# 2_MaxWatch.net
KiCad netlist of a schematic drawn in Altium Designer
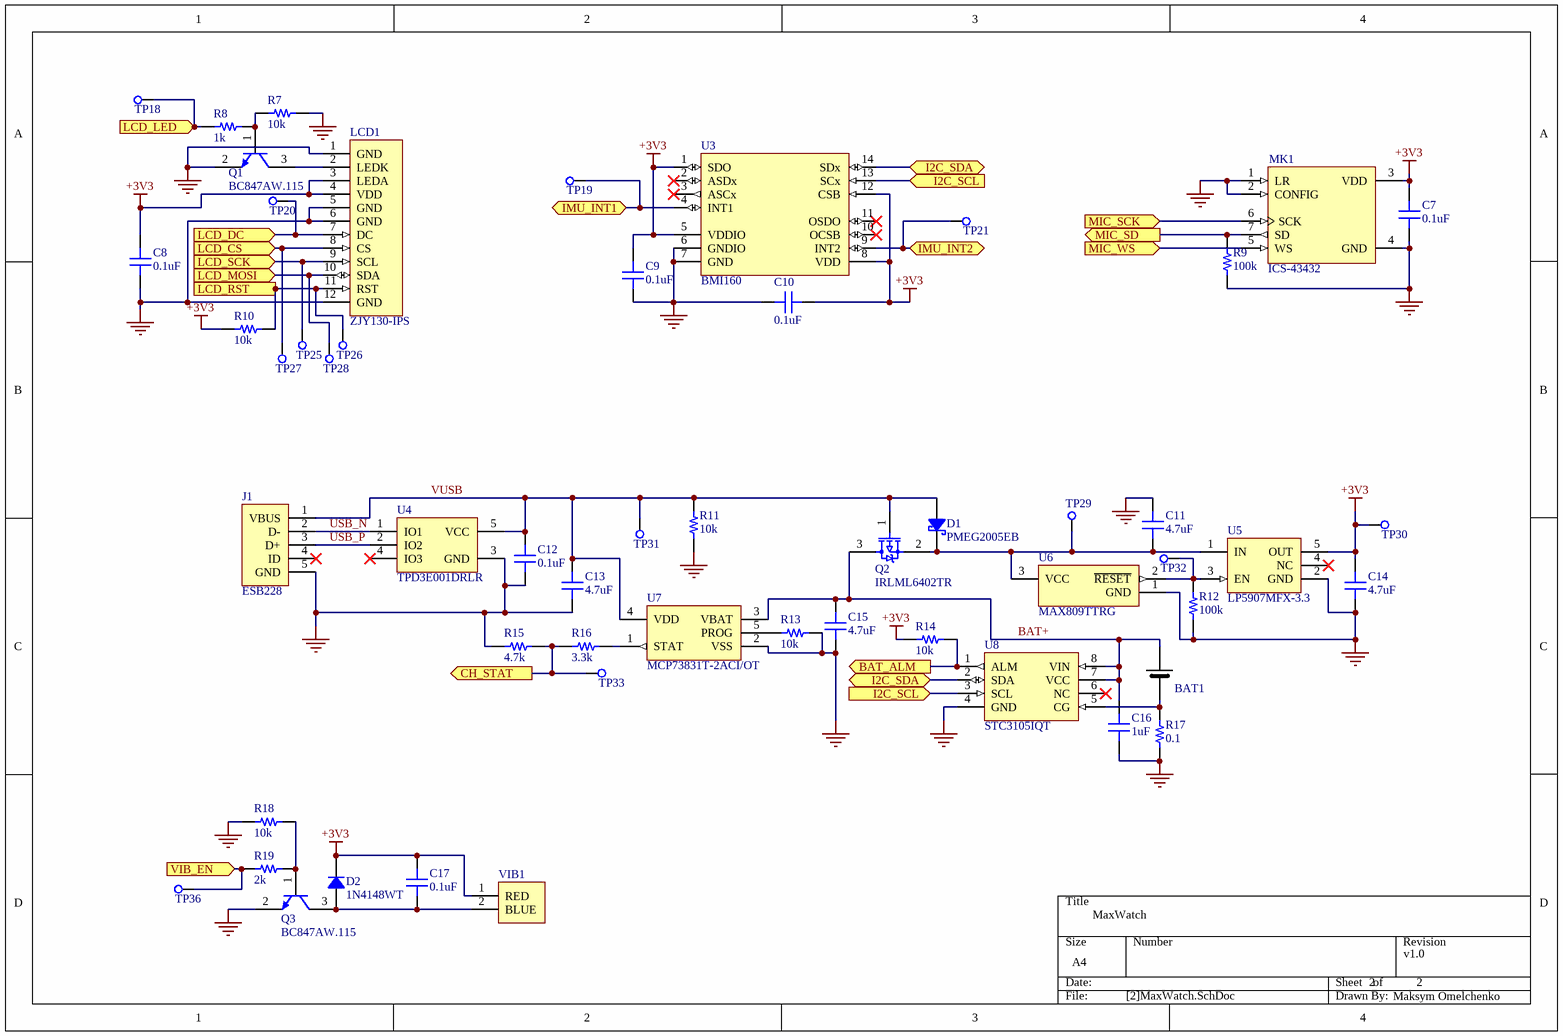
[diagram p0: [2]MaxWatch.SchDoc]

(export (version "E")
  (design (tool "Eeschema 10.0.6"))
  (components
    (comp (ref "BAT1")
      (value "Lipo battery")
      (footprint "PCBComponent_1")
      (libsource (lib "Battery") (part "Lipo_battery"))
    )
    (comp (ref "C7")
      (value "0.1uF")
      (footprint "CAP 0402/1005")
      (description "CAP CER 0.1UF 16V X7R 0402")
      (fields
        (field (name "PART NUMBER") "C1005X7R1C104K050BC")
        (field (name "MANUFACTURER") "TDK Corporation")
      )
      (libsource (lib "Celestial Library Database") (part "Capacitor"))
    )
    (comp (ref "C8")
      (value "0.1uF")
      (footprint "CAP 0402/1005")
      (description "CAP CER 0.1UF 16V X7R 0402")
      (fields
        (field (name "PART NUMBER") "C1005X7R1C104K050BC")
        (field (name "MANUFACTURER") "TDK Corporation")
      )
      (libsource (lib "Celestial Library Database") (part "Capacitor"))
    )
    (comp (ref "C9")
      (value "0.1uF")
      (footprint "CAP 0402/1005")
      (description "CAP CER 0.1UF 16V X7R 0402")
      (fields
        (field (name "PART NUMBER") "C1005X7R1C104K050BC")
        (field (name "MANUFACTURER") "TDK Corporation")
      )
      (libsource (lib "Celestial Library Database") (part "Capacitor"))
    )
    (comp (ref "C10")
      (value "0.1uF")
      (footprint "CAP 0402/1005")
      (description "CAP CER 0.1UF 16V X7R 0402")
      (fields
        (field (name "PART NUMBER") "C1005X7R1C104K050BC")
        (field (name "MANUFACTURER") "TDK Corporation")
      )
      (libsource (lib "Celestial Library Database") (part "Capacitor"))
    )
    (comp (ref "C11")
      (value "4.7uF")
      (footprint "CAP 0603/1608")
      (description "CAP CER 4.7UF 6.3V X5R 0603")
      (fields (field (name "PART NUMBER") "JMK107BJ475KA-T") (field (name "MANUFACTURER") "Taiyo Yuden"))
      (libsource (lib "Celestial Library Database") (part "Capacitor"))
    )
    (comp (ref "C12")
      (value "0.1uF")
      (footprint "CAP 0402/1005")
      (description "CAP CER 0.1UF 16V X7R 0402")
      (fields
        (field (name "PART NUMBER") "C1005X7R1C104K050BC")
        (field (name "MANUFACTURER") "TDK Corporation")
      )
      (libsource (lib "Celestial Library Database") (part "Capacitor"))
    )
    (comp (ref "C13")
      (value "4.7uF")
      (footprint "CAP 0603/1608")
      (description "CAP CER 4.7UF 6.3V X5R 0603")
      (fields (field (name "PART NUMBER") "JMK107BJ475KA-T") (field (name "MANUFACTURER") "Taiyo Yuden"))
      (libsource (lib "Celestial Library Database") (part "Capacitor"))
    )
    (comp (ref "C14")
      (value "4.7uF")
      (footprint "CAP 0603/1608")
      (description "CAP CER 4.7UF 6.3V X5R 0603")
      (fields (field (name "PART NUMBER") "JMK107BJ475KA-T") (field (name "MANUFACTURER") "Taiyo Yuden"))
      (libsource (lib "Celestial Library Database") (part "Capacitor"))
    )
    (comp (ref "C15")
      (value "4.7uF")
      (footprint "CAP 0603/1608")
      (description "CAP CER 4.7UF 6.3V X5R 0603")
      (fields (field (name "PART NUMBER") "JMK107BJ475KA-T") (field (name "MANUFACTURER") "Taiyo Yuden"))
      (libsource (lib "Celestial Library Database") (part "Capacitor"))
    )
    (comp (ref "C16")
      (value "1uF")
      (footprint "CAP 0402/1005")
      (description "CAP CER 1UF 4V X7R 0402")
      (fields
        (field (name "PART NUMBER") "GRM155R70G105KA12D")
        (field (name "MANUFACTURER") "Murata Electronics North America")
      )
      (libsource (lib "Celestial Library Database") (part "Capacitor"))
    )
    (comp (ref "C17")
      (value "0.1uF")
      (footprint "CAP 0402/1005")
      (description "CAP CER 0.1UF 16V X7R 0402")
      (fields
        (field (name "PART NUMBER") "C1005X7R1C104K050BC")
        (field (name "MANUFACTURER") "TDK Corporation")
      )
      (libsource (lib "Celestial Library Database") (part "Capacitor"))
    )
    (comp (ref "D1")
      (value "PMEG2005EB")
      (footprint "NXP-SOD-523F-2_V")
      (fields (field (name "MANUFACTURER") "Nexperia") (field (name "MODEL") "PMEG2005EB"))
      (libsource (lib "Nexperia_PMEG2005EB") (part "PMEG2005EB"))
    )
    (comp (ref "D2")
      (value "1N4148WT")
      (footprint "FAIR-SOD-523F-2_V")
      (description "High Conductance Fast Switching Diode, 75 V, -55 to 150 degC, 2-Pin SOD523F, RoHS")
      (fields (field (name "MANUFACTURER") "Fairchild Semiconductor") (field (name "PARTNUMBER") "1N4148WT"))
      (libsource (lib "1N4148WT") (part "1N4148WT"))
    )
    (comp (ref "J1")
      (value "ESB228")
      (footprint "EXB228")
      (fields (field (name "MODEL") "ESB228"))
      (libsource (lib "ESB228") (part "ESB228"))
    )
    (comp (ref "LCD1")
      (value "ZJY130-IPS ST7789 based lcd display")
      (footprint "ZJY130-IPS")
      (fields (field (name "MODEL") "ZJY130-IPS"))
      (libsource (lib "ZJY130-IPS") (part "ZJY130-IPS"))
    )
    (comp (ref "MK1")
      (value "ICS-43432")
      (footprint "MIC_ICS-43432")
      (description "A high performance, low power, digital output, omnidirectional MEMS microphone with a bottom port.")
      (fields (field (name "MF") "TDK InvenSense") (field (name "MODEL") "ICS-43432"))
      (libsource (lib "ICS-43432") (part "ICS-43432"))
    )
    (comp (ref "Q1")
      (value "BC847AW")
      (footprint "NEXPERIA-SC-70")
      (description "General Purpose Transistor, NPN Silicon, 3-Pin SC70, Tape and Reel")
      (fields (field (name "MANUFACTURER") "Nexperia") (field (name "MODEL") "BC847AW.115"))
      (libsource (lib "BC847AW") (part "BC847AW"))
    )
    (comp (ref "Q2")
      (value "IRLML6402TRPBF")
      (footprint "Infineon_SOT23")
      (fields (field (name "MANUFACTURER") "Infineon Technologies") (field (name "MODEL") "IRLML6402TR"))
      (libsource (lib "IRLML6402TR") (part "IRLML6402TRPBF"))
    )
    (comp (ref "Q3")
      (value "BC847AW")
      (footprint "NEXPERIA-SC-70")
      (description "General Purpose Transistor, NPN Silicon, 3-Pin SC70, Tape and Reel")
      (fields (field (name "MANUFACTURER") "Nexperia") (field (name "MODEL") "BC847AW.115"))
      (libsource (lib "BC847AW") (part "BC847AW"))
    )
    (comp (ref "R7")
      (value "10k")
      (footprint "RES 0201/0603")
      (description "RES SMD 10K OHM 5% 1/20W 0201")
      (fields (field (name "PART NUMBER") "RC0201JR-0710KL") (field (name "MANUFACTURER") "Yageo"))
      (libsource (lib "Celestial Library Database") (part "Resistor"))
    )
    (comp (ref "R8")
      (value "1k")
      (footprint "RES 0402/1005")
      (description "RES SMD 1K OHM 1% 1/10W 0402")
      (fields
        (field (name "PART NUMBER") "ERJ-2RKF1001X")
        (field (name "MANUFACTURER") "Panasonic Electronic Components")
      )
      (libsource (lib "Celestial Library Database") (part "Resistor"))
    )
    (comp (ref "R9")
      (value "100k")
      (footprint "RES 0402/1005")
      (description "RES SMD 100K OHM 1% 1/10W 0402")
      (fields
        (field (name "PART NUMBER") "ERJ-2RKF1003X")
        (field (name "MANUFACTURER") "Panasonic Electronic Components")
      )
      (libsource (lib "Celestial Library Database") (part "Resistor"))
    )
    (comp (ref "R10")
      (value "10k")
      (footprint "RES 0201/0603")
      (description "RES SMD 10K OHM 5% 1/20W 0201")
      (fields (field (name "PART NUMBER") "RC0201JR-0710KL") (field (name "MANUFACTURER") "Yageo"))
      (libsource (lib "Celestial Library Database") (part "Resistor"))
    )
    (comp (ref "R11")
      (value "10k")
      (footprint "RES 0201/0603")
      (description "RES SMD 10K OHM 5% 1/20W 0201")
      (fields (field (name "PART NUMBER") "RC0201JR-0710KL") (field (name "MANUFACTURER") "Yageo"))
      (libsource (lib "Celestial Library Database") (part "Resistor"))
    )
    (comp (ref "R12")
      (value "100k")
      (footprint "RES 0402/1005")
      (description "RES SMD 100K OHM 1% 1/10W 0402")
      (fields
        (field (name "PART NUMBER") "ERJ-2RKF1003X")
        (field (name "MANUFACTURER") "Panasonic Electronic Components")
      )
      (libsource (lib "Celestial Library Database") (part "Resistor"))
    )
    (comp (ref "R13")
      (value "10k")
      (footprint "RES 0201/0603")
      (description "RES SMD 10K OHM 5% 1/20W 0201")
      (fields (field (name "PART NUMBER") "RC0201JR-0710KL") (field (name "MANUFACTURER") "Yageo"))
      (libsource (lib "Celestial Library Database") (part "Resistor"))
    )
    (comp (ref "R14")
      (value "10k")
      (footprint "RES 0201/0603")
      (description "RES SMD 10K OHM 5% 1/20W 0201")
      (fields (field (name "PART NUMBER") "RC0201JR-0710KL") (field (name "MANUFACTURER") "Yageo"))
      (libsource (lib "Celestial Library Database") (part "Resistor"))
    )
    (comp (ref "R15")
      (value "4.7k")
      (footprint "RES 0402/1005")
      (description "RES SMD 4.7K OHM 1% 1/10W 0402")
      (fields
        (field (name "PART NUMBER") "ERJ-2RKF4701X")
        (field (name "MANUFACTURER") "Panasonic Electronic Components")
      )
      (libsource (lib "Celestial Library Database") (part "Resistor"))
    )
    (comp (ref "R16")
      (value "3.3k")
      (footprint "RES 0402/1005")
      (description "RES SMD 3.3K OHM 1% 1/10W 0402")
      (fields
        (field (name "PART NUMBER") "ERJ-2RKF3301X")
        (field (name "MANUFACTURER") "Panasonic Electronic Components")
      )
      (libsource (lib "Celestial Library Database") (part "Resistor"))
    )
    (comp (ref "R17")
      (value "0.1")
      (footprint "RES 0603/1608")
      (description "RES SMD 0.1 OHM 1% 1/10W 0603")
      (fields
        (field (name "PART NUMBER") "ERJ-3RSFR10V")
        (field (name "MANUFACTURER") "Panasonic Electronic Components")
      )
      (libsource (lib "Celestial Library Database") (part "Resistor"))
    )
    (comp (ref "R18")
      (value "10k")
      (footprint "RES 0201/0603")
      (description "RES SMD 10K OHM 5% 1/20W 0201")
      (fields (field (name "PART NUMBER") "RC0201JR-0710KL") (field (name "MANUFACTURER") "Yageo"))
      (libsource (lib "Celestial Library Database") (part "Resistor"))
    )
    (comp (ref "R19")
      (value "2k")
      (footprint "RES 0402/1005")
      (description "RES SMD 2K OHM 1% 1/10W 0402")
      (fields
        (field (name "PART NUMBER") "ERJ-2RKF2001X")
        (field (name "MANUFACTURER") "Panasonic Electronic Components")
      )
      (libsource (lib "Celestial Library Database") (part "Resistor"))
    )
    (comp (ref "TP18") (value "TP") (footprint "TP_0.75x0.75") (libsource (lib "TestPoint") (part "TP")))
    (comp (ref "TP19") (value "TP") (footprint "TP_0.75x0.75") (libsource (lib "TestPoint") (part "TP")))
    (comp (ref "TP20") (value "TP") (footprint "TP_0.75x0.75") (libsource (lib "TestPoint") (part "TP")))
    (comp (ref "TP21") (value "TP") (footprint "TP_0.75x0.75") (libsource (lib "TestPoint") (part "TP")))
    (comp (ref "TP25") (value "TP") (footprint "TP_0.75x0.75") (libsource (lib "TestPoint") (part "TP")))
    (comp (ref "TP26") (value "TP") (footprint "TP_0.75x0.75") (libsource (lib "TestPoint") (part "TP")))
    (comp (ref "TP27") (value "TP") (footprint "TP_0.75x0.75") (libsource (lib "TestPoint") (part "TP")))
    (comp (ref "TP28") (value "TP") (footprint "TP_0.75x0.75") (libsource (lib "TestPoint") (part "TP")))
    (comp (ref "TP29") (value "TP") (footprint "TP_0.75x0.75") (libsource (lib "TestPoint") (part "TP")))
    (comp (ref "TP30") (value "TP") (footprint "TP_0.75x0.75") (libsource (lib "TestPoint") (part "TP")))
    (comp (ref "TP31") (value "TP") (footprint "TP_0.75x0.75") (libsource (lib "TestPoint") (part "TP")))
    (comp (ref "TP32") (value "TP") (footprint "TP_0.75x0.75") (libsource (lib "TestPoint") (part "TP")))
    (comp (ref "TP33") (value "TP") (footprint "TP_0.75x0.75") (libsource (lib "TestPoint") (part "TP")))
    (comp (ref "TP36") (value "TP") (footprint "TP_0.75x0.75") (libsource (lib "TestPoint") (part "TP")))
    (comp (ref "U3")
      (value "BMI160")
      (footprint "BMI160-LGA14")
      (libsource (lib "Sensors_lib") (part "BMI160"))
    )
    (comp (ref "U4")
      (value "TPD3E001DRLR")
      (footprint "DRL0005A")
      (fields (field (name "MANUFACTURER") "Texas Instruments") (field (name "PARTNUMBER") "TPD3E001DRLR"))
      (libsource (lib "TPD3E001DRLR") (part "TPD3E001DRLR"))
    )
    (comp (ref "U5")
      (value "LP5907MFX-3.3-NOPB")
      (footprint "Texas_Instruments_DBV0005A_0")
      (fields (field (name "MANUFACTURER") "Texas Instruments") (field (name "MODEL") "LP5907MFX-3.3"))
      (libsource (lib "LP5907MFX-3.3") (part "LP5907MFX-3.3-NOPB"))
    )
    (comp (ref "U6")
      (value "IC_ON_Semi_MAX809TTRG")
      (footprint "ON_Semi_CASE_318-08_0")
      (description "IC MPU SUPERVISORY 3.08V SOT23")
      (fields (field (name "MANUFACTURER") "ON Semi") (field (name "PART NUMBER") "MAX809TTRG"))
      (libsource (lib "MAX809TTRG") (part "IC_ON_Semi_MAX809TTRG"))
    )
    (comp (ref "U7")
      (value "MCP73831T-2ACI/OT")
      (footprint "SOT-23-OT5_L")
      (fields (field (name "MODEL") "MCP73831T-2ACI/OT"))
      (libsource (lib "MCP73831T_2ACI_OT") (part "MCP73831T-2ACI/OT"))
    )
    (comp (ref "U8")
      (value "IC_STMicroelectronics_STC3105IQT_eec")
      (footprint "STMicroelectronics_STC3105IQT_0")
      (description "IC Battery Battery Monitor IC 8-TDFN (3x2)")
      (fields
        (field (name "VOLTAGE") "2.7V~5.5V")
        (field (name "MANUFACTURER") "STMicroelectronics")
        (field (name "PART NUMBER") "STC3105IQT")
      )
      (libsource (lib "STC3105IQT") (part "IC_STMicroelectronics_STC3105IQT_eec"))
    )
    (comp (ref "VIB1")
      (value "Vibrating Motor 0408")
      (footprint "Vibrating_Motor")
      (libsource (lib "VIBRO") (part "Vibrating Motor"))
    )
  )
  (nets
    (net (code "1") (name "+3V3") (class "Default")
      (node (ref "C10") (pin "2") (pinfunction "2_2") (pintype "passive"))
      (node (ref "C14") (pin "2") (pinfunction "2_2") (pintype "passive"))
      (node (ref "C17") (pin "2") (pinfunction "2_2") (pintype "passive"))
      (node (ref "C7") (pin "2") (pinfunction "2_2") (pintype "passive"))
      (node (ref "C8") (pin "2") (pinfunction "2_2") (pintype "passive"))
      (node (ref "C9") (pin "2") (pinfunction "2_2") (pintype "passive"))
      (node (ref "D2") (pin "2") (pinfunction "2_2") (pintype "passive"))
      (node (ref "LCD1") (pin "3") (pinfunction "LEDA_3") (pintype "power_in"))
      (node (ref "LCD1") (pin "4") (pinfunction "VDD_4") (pintype "power_in"))
      (node (ref "MK1") (pin "3") (pinfunction "VDD_3") (pintype "power_in"))
      (node (ref "R10") (pin "2") (pinfunction "2_2") (pintype "passive"))
      (node (ref "R14") (pin "2") (pinfunction "2_2") (pintype "passive"))
      (node (ref "TP30") (pin "1") (pinfunction "TP_1") (pintype "passive"))
      (node (ref "U3") (pin "1") (pinfunction "SDO_1") (pintype "bidirectional"))
      (node (ref "U3") (pin "12") (pinfunction "CSB_12") (pintype "input"))
      (node (ref "U3") (pin "5") (pinfunction "VDDIO_5") (pintype "power_in"))
      (node (ref "U3") (pin "8") (pinfunction "VDD_8") (pintype "power_in"))
      (node (ref "U5") (pin "5") (pinfunction "OUT_5") (pintype "power_in"))
      (node (ref "VIB1") (pin "1") (pinfunction "RED_1") (pintype "passive"))
    )
    (net (code "2") (name "/BAT+") (class "Default")
      (node (ref "BAT1") (pin "1") (pintype "passive"))
      (node (ref "C15") (pin "2") (pinfunction "2_2") (pintype "passive"))
      (node (ref "C16") (pin "2") (pinfunction "2_2") (pintype "passive"))
      (node (ref "Q2") (pin "3") (pinfunction "D_3") (pintype "passive"))
      (node (ref "U7") (pin "3") (pinfunction "VBAT_3") (pintype "power_in"))
      (node (ref "U8") (pin "7") (pinfunction "VCC_7") (pintype "power_in"))
      (node (ref "U8") (pin "8") (pinfunction "VIN_8") (pintype "input"))
    )
    (net (code "3") (name "/BAT_ALM") (class "Default")
      (node (ref "R14") (pin "1") (pinfunction "1_1") (pintype "passive"))
      (node (ref "U8") (pin "1") (pinfunction "ALM_1") (pintype "output"))
    )
    (net (code "4") (name "/CH_STAT") (class "Default")
      (node (ref "R15") (pin "1") (pinfunction "1_1") (pintype "passive"))
      (node (ref "R16") (pin "1") (pinfunction "1_1") (pintype "passive"))
      (node (ref "TP33") (pin "1") (pinfunction "TP_1") (pintype "passive"))
    )
    (net (code "5") (name "/I2C_SCL") (class "Default")
      (node (ref "U3") (pin "13") (pinfunction "SCx_13") (pintype "input"))
      (node (ref "U8") (pin "3") (pinfunction "SCL_3") (pintype "input"))
    )
    (net (code "6") (name "/I2C_SDA") (class "Default")
      (node (ref "U3") (pin "14") (pinfunction "SDx_14") (pintype "bidirectional"))
      (node (ref "U8") (pin "2") (pinfunction "SDA_2") (pintype "bidirectional"))
    )
    (net (code "7") (name "/IMU_INT1") (class "Default")
      (node (ref "TP19") (pin "1") (pinfunction "TP_1") (pintype "passive"))
      (node (ref "U3") (pin "4") (pinfunction "INT1_4") (pintype "bidirectional"))
    )
    (net (code "8") (name "/IMU_INT2") (class "Default")
      (node (ref "TP21") (pin "1") (pinfunction "TP_1") (pintype "passive"))
      (node (ref "U3") (pin "9") (pinfunction "INT2_9") (pintype "bidirectional"))
    )
    (net (code "9") (name "/LCD_CS") (class "Default")
      (node (ref "LCD1") (pin "8") (pinfunction "CS_8") (pintype "input"))
      (node (ref "TP27") (pin "1") (pinfunction "TP_1") (pintype "passive"))
    )
    (net (code "10") (name "/LCD_DC") (class "Default")
      (node (ref "LCD1") (pin "7") (pinfunction "DC_7") (pintype "input"))
      (node (ref "TP20") (pin "1") (pinfunction "TP_1") (pintype "passive"))
    )
    (net (code "11") (name "/LCD_LED") (class "Default")
      (node (ref "R8") (pin "1") (pinfunction "1_1") (pintype "passive"))
      (node (ref "TP18") (pin "1") (pinfunction "TP_1") (pintype "passive"))
    )
    (net (code "12") (name "/LCD_MOSI") (class "Default")
      (node (ref "LCD1") (pin "10") (pinfunction "SDA_10") (pintype "bidirectional"))
      (node (ref "TP28") (pin "1") (pinfunction "TP_1") (pintype "passive"))
    )
    (net (code "13") (name "/LCD_RST") (class "Default")
      (node (ref "LCD1") (pin "11") (pinfunction "RST_11") (pintype "input"))
      (node (ref "R10") (pin "1") (pinfunction "1_1") (pintype "passive"))
      (node (ref "TP26") (pin "1") (pinfunction "TP_1") (pintype "passive"))
    )
    (net (code "14") (name "/LCD_SCK") (class "Default")
      (node (ref "LCD1") (pin "9") (pinfunction "SCL_9") (pintype "input"))
      (node (ref "TP25") (pin "1") (pinfunction "TP_1") (pintype "passive"))
    )
    (net (code "15") (name "/MIC_SCK") (class "Default")
      (node (ref "MK1") (pin "6") (pinfunction "SCK_6") (pintype "input"))
    )
    (net (code "16") (name "/MIC_SD") (class "Default")
      (node (ref "MK1") (pin "7") (pinfunction "SD_7") (pintype "output"))
      (node (ref "R9") (pin "2") (pinfunction "2_2") (pintype "passive"))
    )
    (net (code "17") (name "/MIC_WS") (class "Default")
      (node (ref "MK1") (pin "5") (pinfunction "WS_5") (pintype "input"))
    )
    (net (code "18") (name "/USB_N") (class "Default")
      (node (ref "J1") (pin "2") (pinfunction "D-_2") (pintype "passive"))
      (node (ref "U4") (pin "1") (pinfunction "IO1_1") (pintype "passive"))
    )
    (net (code "19") (name "/USB_P") (class "Default")
      (node (ref "J1") (pin "3") (pinfunction "D+_3") (pintype "passive"))
      (node (ref "U4") (pin "2") (pinfunction "IO2_2") (pintype "passive"))
    )
    (net (code "20") (name "/VIB_EN") (class "Default")
      (node (ref "R19") (pin "1") (pinfunction "1_1") (pintype "passive"))
      (node (ref "TP36") (pin "1") (pinfunction "TP_1") (pintype "passive"))
    )
    (net (code "21") (name "/VUSB") (class "Default")
      (node (ref "C12") (pin "2") (pinfunction "2_2") (pintype "passive"))
      (node (ref "C13") (pin "2") (pinfunction "2_2") (pintype "passive"))
      (node (ref "D1") (pin "1") (pinfunction "1_1") (pintype "passive"))
      (node (ref "J1") (pin "1") (pinfunction "VBUS_1") (pintype "passive"))
      (node (ref "Q2") (pin "1") (pinfunction "G_1") (pintype "passive"))
      (node (ref "R11") (pin "2") (pinfunction "2_2") (pintype "passive"))
      (node (ref "TP31") (pin "1") (pinfunction "TP_1") (pintype "passive"))
      (node (ref "U4") (pin "5") (pinfunction "VCC_5") (pintype "power_in"))
      (node (ref "U7") (pin "4") (pinfunction "VDD_4") (pintype "power_in"))
    )
    (net (code "22") (name "GND") (class "Default")
      (node (ref "C10") (pin "1") (pinfunction "1_1") (pintype "passive"))
      (node (ref "C11") (pin "2") (pinfunction "2_2") (pintype "passive"))
      (node (ref "C12") (pin "1") (pinfunction "1_1") (pintype "passive"))
      (node (ref "C13") (pin "1") (pinfunction "1_1") (pintype "passive"))
      (node (ref "C14") (pin "1") (pinfunction "1_1") (pintype "passive"))
      (node (ref "C15") (pin "1") (pinfunction "1_1") (pintype "passive"))
      (node (ref "C16") (pin "1") (pinfunction "1_1") (pintype "passive"))
      (node (ref "C7") (pin "1") (pinfunction "1_1") (pintype "passive"))
      (node (ref "C8") (pin "1") (pinfunction "1_1") (pintype "passive"))
      (node (ref "C9") (pin "1") (pinfunction "1_1") (pintype "passive"))
      (node (ref "J1") (pin "5") (pinfunction "GND_5") (pintype "passive"))
      (node (ref "LCD1") (pin "1") (pinfunction "GND_1") (pintype "power_in"))
      (node (ref "LCD1") (pin "12") (pinfunction "GND_12") (pintype "power_in"))
      (node (ref "LCD1") (pin "5") (pinfunction "GND_5") (pintype "power_in"))
      (node (ref "LCD1") (pin "6") (pinfunction "GND_6") (pintype "power_in"))
      (node (ref "MK1") (pin "1") (pinfunction "LR_1") (pintype "input"))
      (node (ref "MK1") (pin "2") (pinfunction "CONFIG_2") (pintype "input"))
      (node (ref "MK1") (pin "4") (pinfunction "GND_4") (pintype "power_in"))
      (node (ref "Q1") (pin "2") (pinfunction "E_2") (pintype "passive"))
      (node (ref "Q3") (pin "2") (pinfunction "E_2") (pintype "passive"))
      (node (ref "R11") (pin "1") (pinfunction "1_1") (pintype "passive"))
      (node (ref "R12") (pin "1") (pinfunction "1_1") (pintype "passive"))
      (node (ref "R13") (pin "1") (pinfunction "1_1") (pintype "passive"))
      (node (ref "R15") (pin "2") (pinfunction "2_2") (pintype "passive"))
      (node (ref "R17") (pin "2") (pinfunction "2_2") (pintype "passive"))
      (node (ref "R18") (pin "2") (pinfunction "2_2") (pintype "passive"))
      (node (ref "R7") (pin "1") (pinfunction "1_1") (pintype "passive"))
      (node (ref "R9") (pin "1") (pinfunction "1_1") (pintype "passive"))
      (node (ref "U3") (pin "6") (pinfunction "GNDIO_6") (pintype "power_in"))
      (node (ref "U3") (pin "7") (pinfunction "GND_7") (pintype "power_in"))
      (node (ref "U4") (pin "3") (pinfunction "GND_3") (pintype "power_in"))
      (node (ref "U5") (pin "2") (pinfunction "GND_2") (pintype "power_in"))
      (node (ref "U6") (pin "1") (pinfunction "GND_1") (pintype "power_in"))
      (node (ref "U7") (pin "2") (pinfunction "VSS_2") (pintype "power_in"))
      (node (ref "U8") (pin "4") (pinfunction "GND_4") (pintype "power_in"))
    )
    (net (code "23") (name "Net-(LCD1-LEDK)") (class "Default")
      (node (ref "LCD1") (pin "2") (pinfunction "LEDK_2") (pintype "power_in"))
      (node (ref "Q1") (pin "3") (pinfunction "C_3") (pintype "passive"))
    )
    (net (code "24") (name "Net-(Q1-B)") (class "Default")
      (node (ref "Q1") (pin "1") (pinfunction "B_1") (pintype "passive"))
      (node (ref "R7") (pin "2") (pinfunction "2_2") (pintype "passive"))
      (node (ref "R8") (pin "2") (pinfunction "2_2") (pintype "passive"))
    )
    (net (code "25") (name "Net-(Q2-S)") (class "Default")
      (node (ref "C11") (pin "1") (pinfunction "1_1") (pintype "passive"))
      (node (ref "D1") (pin "2") (pinfunction "2_2") (pintype "passive"))
      (node (ref "Q2") (pin "2") (pinfunction "S_2") (pintype "passive"))
      (node (ref "TP29") (pin "1") (pinfunction "TP_1") (pintype "passive"))
      (node (ref "U5") (pin "1") (pinfunction "IN_1") (pintype "power_in"))
      (node (ref "U6") (pin "3") (pinfunction "VCC_3") (pintype "power_in"))
    )
    (net (code "26") (name "Net-(Q3-B)") (class "Default")
      (node (ref "Q3") (pin "1") (pinfunction "B_1") (pintype "passive"))
      (node (ref "R18") (pin "1") (pinfunction "1_1") (pintype "passive"))
      (node (ref "R19") (pin "2") (pinfunction "2_2") (pintype "passive"))
    )
    (net (code "27") (name "Net-(Q3-C)") (class "Default")
      (node (ref "C17") (pin "1") (pinfunction "1_1") (pintype "passive"))
      (node (ref "D2") (pin "1") (pinfunction "1_1") (pintype "passive"))
      (node (ref "Q3") (pin "3") (pinfunction "C_3") (pintype "passive"))
      (node (ref "VIB1") (pin "2") (pinfunction "BLUE_2") (pintype "passive"))
    )
    (net (code "28") (name "Net-(TP32-TP)") (class "Default")
      (node (ref "R12") (pin "2") (pinfunction "2_2") (pintype "passive"))
      (node (ref "TP32") (pin "1") (pinfunction "TP_1") (pintype "passive"))
      (node (ref "U5") (pin "3") (pinfunction "EN_3") (pintype "input"))
      (node (ref "U6") (pin "2") (pinfunction "~{RESET}_2") (pintype "output"))
    )
    (net (code "29") (name "Net-(U7-PROG)") (class "Default")
      (node (ref "R13") (pin "2") (pinfunction "2_2") (pintype "passive"))
      (node (ref "U7") (pin "5") (pinfunction "PROG_5") (pintype "passive"))
    )
    (net (code "30") (name "Net-(U7-STAT)") (class "Default")
      (node (ref "R16") (pin "2") (pinfunction "2_2") (pintype "passive"))
      (node (ref "U7") (pin "1") (pinfunction "STAT_1") (pintype "output"))
    )
    (net (code "31") (name "Net-(U8-CG)") (class "Default")
      (node (ref "BAT1") (pin "2") (pintype "passive"))
      (node (ref "R17") (pin "1") (pinfunction "1_1") (pintype "passive"))
      (node (ref "U8") (pin "5") (pinfunction "CG_5") (pintype "input"))
    )
    (net (code "32") (name "unconnected-(J1-ID-Pad4)") (class "Default")
      (node (ref "J1") (pin "4") (pinfunction "ID_4") (pintype "passive+no_connect"))
    )
    (net (code "33") (name "unconnected-(U3-ASCx-Pad3)") (class "Default")
      (node (ref "U3") (pin "3") (pinfunction "ASCx_3") (pintype "output+no_connect"))
    )
    (net (code "34") (name "unconnected-(U3-ASDx-Pad2)") (class "Default")
      (node (ref "U3") (pin "2") (pinfunction "ASDx_2") (pintype "bidirectional+no_connect"))
    )
    (net (code "35") (name "unconnected-(U3-OCSB-Pad10)") (class "Default")
      (node (ref "U3") (pin "10") (pinfunction "OCSB_10") (pintype "bidirectional+no_connect"))
    )
    (net (code "36") (name "unconnected-(U3-OSDO-Pad11)") (class "Default")
      (node (ref "U3") (pin "11") (pinfunction "OSDO_11") (pintype "bidirectional+no_connect"))
    )
    (net (code "37") (name "unconnected-(U4-IO3-Pad4)") (class "Default")
      (node (ref "U4") (pin "4") (pinfunction "IO3_4") (pintype "passive+no_connect"))
    )
    (net (code "38") (name "unconnected-(U5-NC-Pad4)") (class "Default")
      (node (ref "U5") (pin "4") (pinfunction "NC_4") (pintype "passive+no_connect"))
    )
    (net (code "39") (name "unconnected-(U8-NC-Pad6)") (class "Default")
      (node (ref "U8") (pin "6") (pinfunction "NC_6") (pintype "passive+no_connect"))
    )
  )
)
